# CH32V305RBT6-R1.net
KiCad netlist of a schematic drawn in Altium Designer
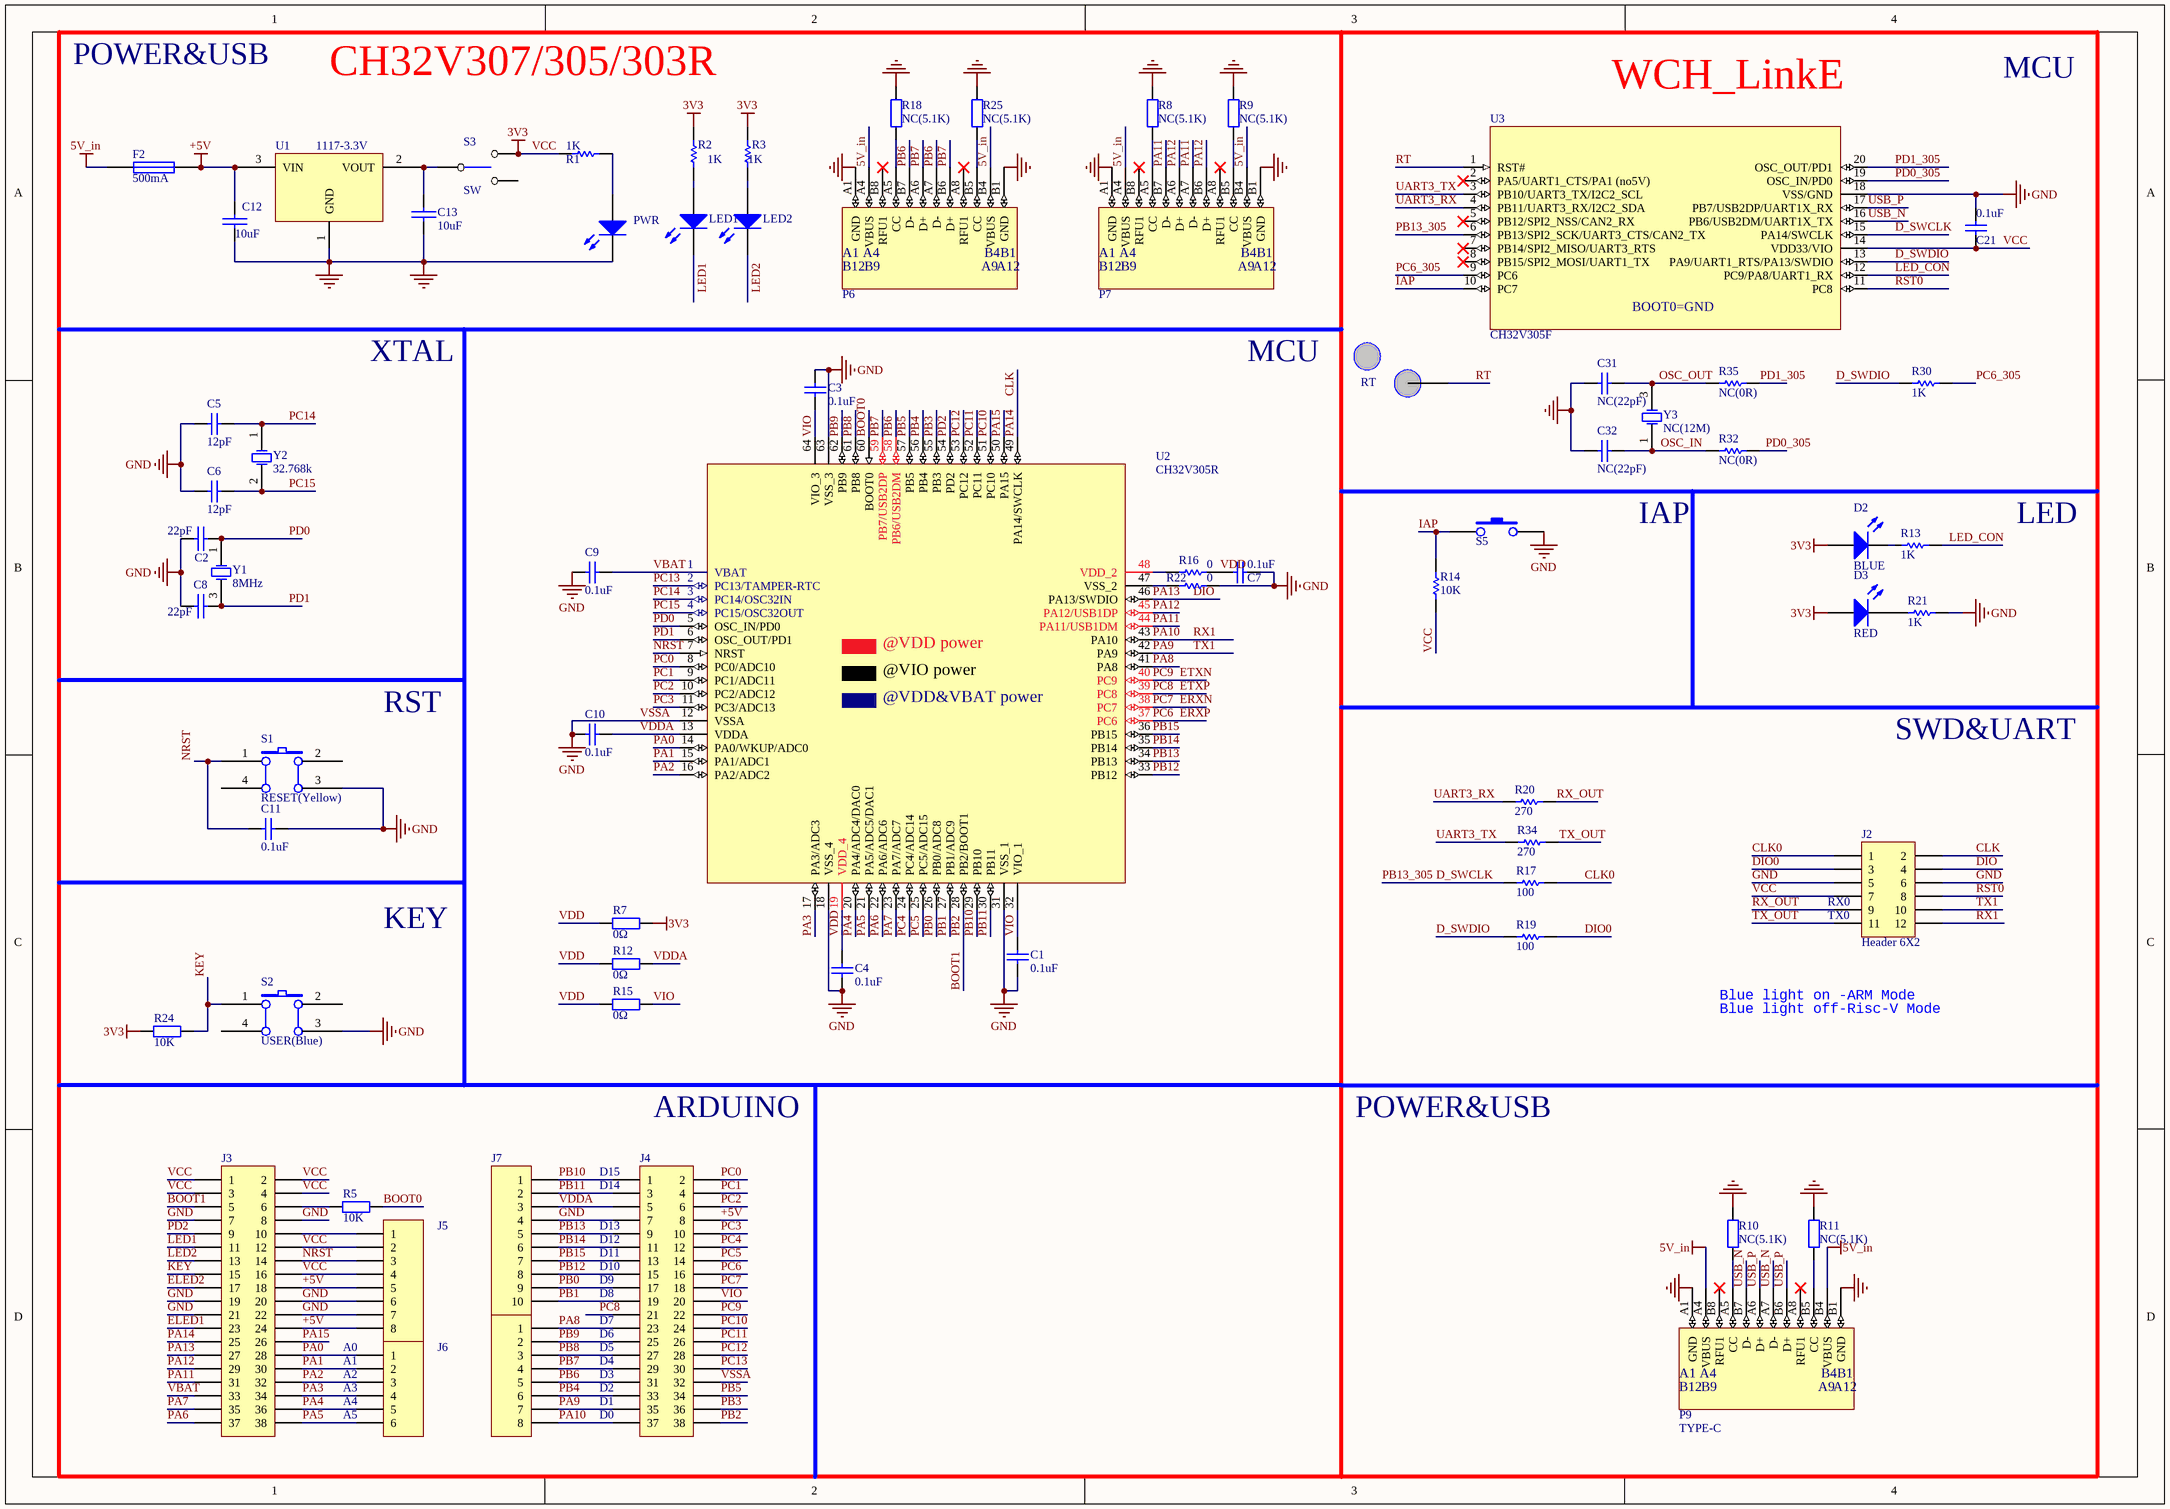
[diagram p0: CH32V305RBT6-R1.SchDoc]

(export (version "E")
  (design (tool "Eeschema 10.0.6"))
  (components
    (comp (ref "C1")
      (value "0.1uF")
      (footprint "0603_C")
      (description "Capacitor")
      (libsource (lib "Miscellaneous Devices") (part "Cap"))
    )
    (comp (ref "C2")
      (value "22pF")
      (footprint "0603_C")
      (description "Capacitor")
      (libsource (lib "*") (part "CAP"))
    )
    (comp (ref "C3")
      (value "0.1uF")
      (footprint "0603_C")
      (description "Capacitor")
      (libsource (lib "Miscellaneous Devices") (part "Cap"))
    )
    (comp (ref "C4")
      (value "0.1uF")
      (footprint "0603_C")
      (description "Capacitor")
      (libsource (lib "Miscellaneous Devices") (part "Cap"))
    )
    (comp (ref "C5")
      (value "12pF")
      (footprint "0603_C")
      (description "Capacitor")
      (libsource (lib "Miscellaneous Devices") (part "Cap"))
    )
    (comp (ref "C6")
      (value "12pF")
      (footprint "0603_C")
      (description "Capacitor")
      (libsource (lib "Miscellaneous Devices") (part "Cap"))
    )
    (comp (ref "C7")
      (value "0.1uF")
      (footprint "0603_C")
      (description "Capacitor")
      (libsource (lib "Miscellaneous Devices") (part "Cap"))
    )
    (comp (ref "C8")
      (value "22pF")
      (footprint "0603_C")
      (description "Capacitor")
      (libsource (lib "*") (part "CAP"))
    )
    (comp (ref "C9")
      (value "0.1uF")
      (footprint "0603_C")
      (description "Capacitor")
      (libsource (lib "Miscellaneous Devices") (part "Cap"))
    )
    (comp (ref "C10")
      (value "0.1uF")
      (footprint "0603_C")
      (description "Capacitor")
      (libsource (lib "Miscellaneous Devices") (part "Cap"))
    )
    (comp (ref "C11")
      (value "0.1uF")
      (footprint "0603_C")
      (description "Capacitor")
      (libsource (lib "Miscellaneous Devices") (part "Cap"))
    )
    (comp (ref "C12")
      (value "10uF")
      (footprint "3216_C")
      (description "Capacitor")
      (libsource (lib "*") (part "CAP"))
    )
    (comp (ref "C13")
      (value "10uF")
      (footprint "3216_C")
      (description "Capacitor")
      (libsource (lib "*") (part "CAP"))
    )
    (comp (ref "C21")
      (value "0.1uF")
      (footprint "0603_C")
      (description "Capacitor")
      (libsource (lib "Miscellaneous Devices") (part "Cap"))
    )
    (comp (ref "C31")
      (value "NC(22pF)")
      (footprint "0603_C")
      (description "Capacitor")
      (fields (field (name "PUBLISHER") "Altium Limited"))
      (libsource (lib "*") (part "Cap"))
    )
    (comp (ref "C32")
      (value "NC(22pF)")
      (footprint "0603_C")
      (description "Capacitor")
      (fields (field (name "PUBLISHER") "Altium Limited"))
      (libsource (lib "*") (part "Cap"))
    )
    (comp (ref "D2")
      (value "BLUE")
      (footprint "0603+")
      (description "Typical RED, GREEN, YELLOW, AMBER GaAs LED")
      (fields (field (name "PUBLISHER") "Altium Limited"))
      (libsource (lib "MYLIB") (part "D0603"))
    )
    (comp (ref "D3")
      (value "RED")
      (footprint "0603+")
      (description "Typical RED, GREEN, YELLOW, AMBER GaAs LED")
      (fields (field (name "PUBLISHER") "Altium Limited"))
      (libsource (lib "MYLIB") (part "D0603"))
    )
    (comp (ref "F2")
      (value "500mA")
      (footprint "0805")
      (description "Fuse")
      (libsource (lib "*") (part "FUSE1"))
    )
    (comp (ref "J2")
      (value "Header 6X2")
      (footprint "IDC12-2.54mm")
      (description "Header, 6-Pin, Dual row")
      (fields (field (name "PUBLISHER") "Altium Limited"))
      (libsource (lib "Miscellaneous Connectors") (part "Header 6X2"))
    )
    (comp (ref "J3")
      (value "Header 19X2")
      (footprint "IDC38-2.54mm")
      (description "Header, 19-Pin, Dual row")
      (fields (field (name "PUBLISHER") "Altium Limited"))
      (libsource (lib "Miscellaneous Connectors") (part "Header 19X2"))
    )
    (comp (ref "J4")
      (value "Header 19X2")
      (footprint "IDC38-2.54mm")
      (description "Header, 19-Pin, Dual row")
      (fields (field (name "PUBLISHER") "Altium Limited"))
      (libsource (lib "Miscellaneous Connectors") (part "Header 19X2"))
    )
    (comp (ref "J5")
      (value "Header 8")
      (footprint "SIP8-2.54mm")
      (description "Header, 8-Pin")
      (fields (field (name "PUBLISHER") "Altium Limited"))
      (libsource (lib "") (part "Header 8_1"))
    )
    (comp (ref "J6")
      (value "Header 6")
      (footprint "SIP6-2.54MM")
      (description "Header, 6-Pin")
      (fields (field (name "PUBLISHER") "Altium Limited"))
      (libsource (lib "Miscellaneous Connectors") (part "Header 6"))
    )
    (comp (ref "J7")
      (value "Header 10")
      (footprint "SIP10-2.54mm")
      (description "Header, 10-Pin")
      (fields (field (name "PUBLISHER") "Altium Limited"))
      (libsource (lib "Miscellaneous Connectors") (part "Header 10"))
    )
    (comp (ref "J8")
      (value "Header 8")
      (footprint "SIP8-2.54mm")
      (description "Header, 8-Pin")
      (fields (field (name "PUBLISHER") "Altium Limited"))
      (libsource (lib "Miscellaneous Connectors") (part "Header 8"))
    )
    (comp (ref "LED1")
      (value "LED1   blue")
      (footprint "0603+")
      (description "Typical INFRARED GaAs LED")
      (fields (field (name "PUBLISHER") "Altium Limited"))
      (libsource (lib "Miscellaneous Devices") (part "LED0"))
    )
    (comp (ref "LED2")
      (value "LED2  blue")
      (footprint "0603+")
      (description "Typical INFRARED GaAs LED")
      (fields (field (name "PUBLISHER") "Altium Limited"))
      (libsource (lib "Miscellaneous Devices") (part "LED0"))
    )
    (comp (ref "P6")
      (value "TYPE-C")
      (footprint "TYPE-C-Receptacle-2.0")
      (libsource (lib "*") (part "TYPE-C1"))
    )
    (comp (ref "P7")
      (value "TYPE-C")
      (footprint "TYPE-C-Receptacle-2.0")
      (libsource (lib "*") (part "TYPE-C1"))
    )
    (comp (ref "P9")
      (value "TYPE-C")
      (footprint "TYPE-C-Receptacle-2.0")
      (libsource (lib "*") (part "TYPE-C1"))
    )
    (comp (ref "PWR")
      (value "POWER  red")
      (footprint "0603+")
      (description "Typical INFRARED GaAs LED")
      (fields (field (name "PUBLISHER") "Altium Limited"))
      (libsource (lib "Miscellaneous Devices") (part "LED0"))
    )
    (comp (ref "R1")
      (value "1K")
      (footprint "0603")
      (description "Semiconductor Resistor")
      (libsource (lib "Miscellaneous Devices") (part "Res Semi"))
    )
    (comp (ref "R2")
      (value "1K")
      (footprint "0603")
      (description "Semiconductor Resistor")
      (libsource (lib "Miscellaneous Devices") (part "Res Semi"))
    )
    (comp (ref "R3")
      (value "1K")
      (footprint "0603")
      (description "Semiconductor Resistor")
      (libsource (lib "Miscellaneous Devices") (part "Res Semi"))
    )
    (comp (ref "R5")
      (value "10K")
      (footprint "0603")
      (description "Resistor")
      (libsource (lib "") (part "Res2_1"))
    )
    (comp (ref "R7")
      (value "0Ω")
      (footprint "0603")
      (description "Resistor")
      (libsource (lib "Miscellaneous Devices") (part "Res2"))
    )
    (comp (ref "R8")
      (value "NC(5.1K)")
      (footprint "0603")
      (description "Resistor")
      (libsource (lib "") (part "Res2_3"))
    )
    (comp (ref "R9")
      (value "NC(5.1K)")
      (footprint "0603")
      (description "Resistor")
      (libsource (lib "") (part "Res2_3"))
    )
    (comp (ref "R10")
      (value "NC(5.1K)")
      (footprint "0603")
      (description "Resistor")
      (libsource (lib "") (part "Res2_2"))
    )
    (comp (ref "R11")
      (value "NC(5.1K)")
      (footprint "0603")
      (description "Resistor")
      (libsource (lib "") (part "Res2_2"))
    )
    (comp (ref "R12")
      (value "0Ω")
      (footprint "0603")
      (description "Resistor")
      (libsource (lib "Miscellaneous Devices") (part "Res2"))
    )
    (comp (ref "R13")
      (value "1K")
      (footprint "0603")
      (description "Resistor")
      (fields (field (name "PUBLISHER") "Altium Limited"))
      (libsource (lib "MYLIB") (part "0603-1"))
    )
    (comp (ref "R14")
      (value "10K")
      (footprint "0603")
      (description "Resistor")
      (fields (field (name "PUBLISHER") "Altium Limited"))
      (libsource (lib "MYLIB") (part "0603-1"))
    )
    (comp (ref "R15")
      (value "0Ω")
      (footprint "0603")
      (description "Resistor")
      (libsource (lib "Miscellaneous Devices") (part "Res2"))
    )
    (comp (ref "R16")
      (value "0")
      (footprint "0603")
      (description "Resistor")
      (fields (field (name "PUBLISHER") "Altium Limited"))
      (libsource (lib "MYLIB") (part "0603-1"))
    )
    (comp (ref "R17")
      (value "100")
      (footprint "0603")
      (description "Resistor")
      (fields (field (name "PUBLISHER") "Altium Limited"))
      (libsource (lib "MYLIB") (part "0603-1"))
    )
    (comp (ref "R18")
      (value "NC(5.1K)")
      (footprint "0603")
      (description "Resistor")
      (libsource (lib "") (part "Res2_3"))
    )
    (comp (ref "R19")
      (value "100")
      (footprint "0603")
      (description "Resistor")
      (fields (field (name "PUBLISHER") "Altium Limited"))
      (libsource (lib "MYLIB") (part "0603-1"))
    )
    (comp (ref "R20")
      (value "270")
      (footprint "0603")
      (description "Resistor")
      (fields (field (name "PUBLISHER") "Altium Limited"))
      (libsource (lib "MYLIB") (part "0603-1"))
    )
    (comp (ref "R21")
      (value "1K")
      (footprint "0603")
      (description "Resistor")
      (fields (field (name "PUBLISHER") "Altium Limited"))
      (libsource (lib "MYLIB") (part "0603-1"))
    )
    (comp (ref "R22")
      (value "0")
      (footprint "0603")
      (description "Resistor")
      (fields (field (name "PUBLISHER") "Altium Limited"))
      (libsource (lib "MYLIB") (part "0603-1"))
    )
    (comp (ref "R24")
      (value "10K")
      (footprint "0603")
      (description "Resistor")
      (libsource (lib "Miscellaneous Devices") (part "Res2"))
    )
    (comp (ref "R25")
      (value "NC(5.1K)")
      (footprint "0603")
      (description "Resistor")
      (libsource (lib "") (part "Res2_3"))
    )
    (comp (ref "R30")
      (value "1K")
      (footprint "0603")
      (description "Resistor")
      (fields (field (name "PUBLISHER") "Altium Limited"))
      (libsource (lib "MYLIB") (part "0603-1"))
    )
    (comp (ref "R32")
      (value "NC(0R)")
      (footprint "0603")
      (description "Resistor")
      (fields (field (name "PUBLISHER") "Altium Limited"))
      (libsource (lib "MYLIB") (part "0603-1"))
    )
    (comp (ref "R34")
      (value "270")
      (footprint "0603")
      (description "Resistor")
      (fields (field (name "PUBLISHER") "Altium Limited"))
      (libsource (lib "MYLIB") (part "0603-1"))
    )
    (comp (ref "R35")
      (value "NC(0R)")
      (footprint "0603")
      (description "Resistor")
      (fields (field (name "PUBLISHER") "Altium Limited"))
      (libsource (lib "MYLIB") (part "0603-1"))
    )
    (comp (ref "RT")
      (value "Testpoint")
      (footprint "TESTPOINT1")
      (description "测试点")
      (libsource (lib "wch_sch_others") (part "Testpoint"))
    )
    (comp (ref "S1")
      (value "RESET(Yellow)")
      (footprint "KEYX")
      (description "SE PUSHBUTTON")
      (libsource (lib "Documents") (part "SW PUSHBUTTON"))
    )
    (comp (ref "S2")
      (value "USER(Blue)")
      (footprint "KEYX")
      (description "SE PUSHBUTTON")
      (libsource (lib "Documents") (part "SW PUSHBUTTON"))
    )
    (comp (ref "S3") (value "SW") (footprint "SW1") (libsource (lib "MYSCH") (part "SW")))
    (comp (ref "S5") (value "KEY") (footprint "贴片按键") (libsource (lib "*") (part "KEY")))
    (comp (ref "U1")
      (value "1117-3.3V")
      (footprint "SOT-223")
      (libsource (lib "wch_sch_others") (part "1117-3.3V"))
    )
    (comp (ref "U2")
      (value "CH32V305R")
      (footprint "LQFP64M_10x10")
      (description "RISC-V FPU HD-MCU, 144MHz, USB_480M, USB OTG, 2*CAN, 4*OPA")
      (libsource (lib "CHXXX") (part "CH32V305R"))
    )
    (comp (ref "U3")
      (value "CH32V305F")
      (footprint "TSSOP20")
      (description "RISC-V FPU HD-MCU, 144MHz, USB_480M, CAN, UART*2, SPI")
      (libsource (lib "CHXXX") (part "CH32V305F"))
    )
    (comp (ref "Y1")
      (value "8MHz")
      (footprint "XT3225")
      (description "Crystal Oscillator")
      (fields (field (name "PUBLISHER") "Altium Limited"))
      (libsource (lib "*") (part "XTAL"))
    )
    (comp (ref "Y2")
      (value "32.768k")
      (footprint "FC-135")
      (description "Crystal Oscillator")
      (fields (field (name "PUBLISHER") "Altium Limited"))
      (libsource (lib "Miscellaneous Devices") (part "XTAL"))
    )
    (comp (ref "Y3")
      (value "NC(12M)")
      (footprint "XT3225")
      (description "Crystal Oscillator")
      (libsource (lib "*") (part "XTAL"))
    )
  )
  (nets
    (net (code "1") (name "+5V") (class "Default")
      (node (ref "C12") (pin "1") (pinfunction "1_1") (pintype "passive"))
      (node (ref "F2") (pin "2") (pinfunction "2_2") (pintype "passive"))
      (node (ref "J3") (pin "18") (pinfunction "18_18") (pintype "passive"))
      (node (ref "J3") (pin "24") (pinfunction "24_24") (pintype "passive"))
      (node (ref "J4") (pin "8") (pinfunction "8_8") (pintype "passive"))
      (node (ref "J5") (pin "5") (pinfunction "5_5") (pintype "passive"))
      (node (ref "J5") (pin "8") (pinfunction "8_8") (pintype "passive"))
      (node (ref "U1") (pin "3") (pinfunction "VIN_3") (pintype "passive"))
    )
    (net (code "2") (name "/BOOT0") (class "Default")
      (node (ref "R5") (pin "2") (pinfunction "2_2") (pintype "passive"))
      (node (ref "U2") (pin "60") (pinfunction "BOOT0_60") (pintype "input"))
    )
    (net (code "3") (name "/BOOT1") (class "Default")
      (node (ref "J3") (pin "5") (pinfunction "5_5") (pintype "passive"))
      (node (ref "J4") (pin "38") (pinfunction "38_38") (pintype "passive"))
      (node (ref "U2") (pin "28") (pinfunction "PB2/BOOT1_28") (pintype "bidirectional"))
    )
    (net (code "4") (name "/CLK") (class "Default")
      (node (ref "J2") (pin "2") (pinfunction "2_2") (pintype "passive"))
      (node (ref "J3") (pin "25") (pinfunction "25_25") (pintype "passive"))
      (node (ref "U2") (pin "49") (pinfunction "PA14/SWCLK_49") (pintype "bidirectional"))
    )
    (net (code "5") (name "/CLK0") (class "Default")
      (node (ref "J2") (pin "1") (pinfunction "1_1") (pintype "passive"))
      (node (ref "R17") (pin "1") (pinfunction "1_1") (pintype "passive"))
    )
    (net (code "6") (name "/DIO") (class "Default")
      (node (ref "J2") (pin "4") (pinfunction "4_4") (pintype "passive"))
      (node (ref "J3") (pin "27") (pinfunction "27_27") (pintype "passive"))
      (node (ref "U2") (pin "46") (pinfunction "PA13/SWDIO_46") (pintype "bidirectional"))
    )
    (net (code "7") (name "/DIO0") (class "Default")
      (node (ref "J2") (pin "3") (pinfunction "3_3") (pintype "passive"))
      (node (ref "R19") (pin "1") (pinfunction "1_1") (pintype "passive"))
    )
    (net (code "8") (name "/D_SWCLK") (class "Default")
      (node (ref "R17") (pin "2") (pinfunction "2_2") (pintype "passive"))
      (node (ref "U3") (pin "15") (pinfunction "PA14/SWCLK_15") (pintype "bidirectional"))
      (node (ref "U3") (pin "6") (pinfunction "PB13/SPI2_SCK/UART3_CTS/CAN2_TX_6") (pintype "bidirectional"))
    )
    (net (code "9") (name "/D_SWDIO") (class "Default")
      (node (ref "R19") (pin "2") (pinfunction "2_2") (pintype "passive"))
      (node (ref "R30") (pin "1") (pinfunction "1_1") (pintype "passive"))
      (node (ref "U3") (pin "13") (pinfunction "PA9/UART1_RTS/PA13/SWDIO_13") (pintype "bidirectional"))
    )
    (net (code "10") (name "/ELED1") (class "Default")
      (node (ref "J3") (pin "23") (pinfunction "23_23") (pintype "passive"))
    )
    (net (code "11") (name "/ELED2") (class "Default")
      (node (ref "J3") (pin "17") (pinfunction "17_17") (pintype "passive"))
    )
    (net (code "12") (name "/ERXN") (class "Default")
      (node (ref "J4") (pin "18") (pinfunction "18_18") (pintype "passive"))
      (node (ref "U2") (pin "38") (pinfunction "PC7_38") (pintype "bidirectional"))
    )
    (net (code "13") (name "/ERXP") (class "Default")
      (node (ref "J4") (pin "16") (pinfunction "16_16") (pintype "passive"))
      (node (ref "U2") (pin "37") (pinfunction "PC6_37") (pintype "bidirectional"))
    )
    (net (code "14") (name "/ETXN") (class "Default")
      (node (ref "J4") (pin "22") (pinfunction "22_22") (pintype "passive"))
      (node (ref "U2") (pin "40") (pinfunction "PC9_40") (pintype "bidirectional"))
    )
    (net (code "15") (name "/ETXP") (class "Default")
      (node (ref "J4") (pin "21") (pinfunction "21_21") (pintype "passive"))
      (node (ref "U2") (pin "39") (pinfunction "PC8_39") (pintype "bidirectional"))
    )
    (net (code "16") (name "/IAP") (class "Default")
      (node (ref "R14") (pin "1") (pinfunction "1_1") (pintype "passive"))
      (node (ref "S5") (pin "1") (pinfunction "1_1") (pintype "passive"))
      (node (ref "U3") (pin "10") (pinfunction "PC7_10") (pintype "bidirectional"))
    )
    (net (code "17") (name "/KEY") (class "Default")
      (node (ref "J3") (pin "15") (pinfunction "15_15") (pintype "passive"))
      (node (ref "R24") (pin "1") (pinfunction "1_1") (pintype "passive"))
      (node (ref "S2") (pin "1") (pinfunction "A0_1") (pintype "passive"))
    )
    (net (code "18") (name "/LED1") (class "Default")
      (node (ref "J3") (pin "11") (pinfunction "11_11") (pintype "passive"))
      (node (ref "LED1") (pin "2") (pinfunction "K_2") (pintype "passive"))
    )
    (net (code "19") (name "/LED2") (class "Default")
      (node (ref "J3") (pin "13") (pinfunction "13_13") (pintype "passive"))
      (node (ref "LED2") (pin "2") (pinfunction "K_2") (pintype "passive"))
    )
    (net (code "20") (name "/LED_CON") (class "Default")
      (node (ref "R13") (pin "1") (pinfunction "1_1") (pintype "passive"))
      (node (ref "U3") (pin "12") (pinfunction "PC9/PA8/UART1_RX_12") (pintype "bidirectional"))
    )
    (net (code "21") (name "/NRST") (class "Default")
      (node (ref "C11") (pin "2") (pinfunction "2_2") (pintype "passive"))
      (node (ref "J3") (pin "14") (pinfunction "14_14") (pintype "passive"))
      (node (ref "J5") (pin "3") (pinfunction "3_3") (pintype "passive"))
      (node (ref "S1") (pin "1") (pinfunction "A0_1") (pintype "passive"))
      (node (ref "U2") (pin "7") (pinfunction "NRST_7") (pintype "input"))
    )
    (net (code "22") (name "/OSC_IN") (class "Default")
      (node (ref "C32") (pin "2") (pinfunction "2_2") (pintype "passive"))
      (node (ref "R32") (pin "2") (pinfunction "2_2") (pintype "passive"))
      (node (ref "Y3") (pin "1") (pinfunction "OSC1_1") (pintype "passive"))
    )
    (net (code "23") (name "/OSC_OUT") (class "Default")
      (node (ref "C31") (pin "2") (pinfunction "2_2") (pintype "passive"))
      (node (ref "R35") (pin "2") (pinfunction "2_2") (pintype "passive"))
      (node (ref "Y3") (pin "3") (pinfunction "OSC2_3") (pintype "passive"))
    )
    (net (code "24") (name "/PA0") (class "Default")
      (node (ref "J3") (pin "28") (pinfunction "28_28") (pintype "passive"))
      (node (ref "J6") (pin "1") (pinfunction "1_1") (pintype "passive"))
      (node (ref "U2") (pin "14") (pinfunction "PA0/WKUP/ADC0_14") (pintype "bidirectional"))
    )
    (net (code "25") (name "/PA1") (class "Default")
      (node (ref "J3") (pin "30") (pinfunction "30_30") (pintype "passive"))
      (node (ref "J6") (pin "2") (pinfunction "2_2") (pintype "passive"))
      (node (ref "U2") (pin "15") (pinfunction "PA1/ADC1_15") (pintype "bidirectional"))
    )
    (net (code "26") (name "/PA2") (class "Default")
      (node (ref "J3") (pin "32") (pinfunction "32_32") (pintype "passive"))
      (node (ref "J6") (pin "3") (pinfunction "3_3") (pintype "passive"))
      (node (ref "U2") (pin "16") (pinfunction "PA2/ADC2_16") (pintype "bidirectional"))
    )
    (net (code "27") (name "/PA3") (class "Default")
      (node (ref "J3") (pin "34") (pinfunction "34_34") (pintype "passive"))
      (node (ref "J6") (pin "4") (pinfunction "4_4") (pintype "passive"))
      (node (ref "U2") (pin "17") (pinfunction "PA3/ADC3_17") (pintype "bidirectional"))
    )
    (net (code "28") (name "/PA4") (class "Default")
      (node (ref "J3") (pin "36") (pinfunction "36_36") (pintype "passive"))
      (node (ref "J6") (pin "5") (pinfunction "5_5") (pintype "passive"))
      (node (ref "U2") (pin "20") (pinfunction "PA4/ADC4/DAC0_20") (pintype "bidirectional"))
    )
    (net (code "29") (name "/PA5") (class "Default")
      (node (ref "J3") (pin "38") (pinfunction "38_38") (pintype "passive"))
      (node (ref "J6") (pin "6") (pinfunction "6_6") (pintype "passive"))
      (node (ref "U2") (pin "21") (pinfunction "PA5/ADC5/DAC1_21") (pintype "bidirectional"))
    )
    (net (code "30") (name "/PA6") (class "Default")
      (node (ref "J3") (pin "37") (pinfunction "37_37") (pintype "passive"))
      (node (ref "U2") (pin "22") (pinfunction "PA6/ADC6_22") (pintype "bidirectional"))
    )
    (net (code "31") (name "/PA7") (class "Default")
      (node (ref "J3") (pin "35") (pinfunction "35_35") (pintype "passive"))
      (node (ref "U2") (pin "23") (pinfunction "PA7/ADC7_23") (pintype "bidirectional"))
    )
    (net (code "32") (name "/PA8") (class "Default")
      (node (ref "J4") (pin "23") (pinfunction "23_23") (pintype "passive"))
      (node (ref "J8") (pin "1") (pinfunction "1_1") (pintype "passive"))
      (node (ref "U2") (pin "41") (pinfunction "PA8_41") (pintype "bidirectional"))
    )
    (net (code "33") (name "/PA9") (class "Default")
      (node (ref "J2") (pin "10") (pinfunction "10_10") (pintype "passive"))
      (node (ref "J4") (pin "35") (pinfunction "35_35") (pintype "passive"))
      (node (ref "J8") (pin "7") (pinfunction "7_7") (pintype "passive"))
      (node (ref "U2") (pin "42") (pinfunction "PA9_42") (pintype "bidirectional"))
    )
    (net (code "34") (name "/PA10") (class "Default")
      (node (ref "J2") (pin "12") (pinfunction "12_12") (pintype "passive"))
      (node (ref "J4") (pin "37") (pinfunction "37_37") (pintype "passive"))
      (node (ref "J8") (pin "8") (pinfunction "8_8") (pintype "passive"))
      (node (ref "U2") (pin "43") (pinfunction "PA10_43") (pintype "bidirectional"))
    )
    (net (code "35") (name "/PA11") (class "Default")
      (node (ref "J3") (pin "31") (pinfunction "31_31") (pintype "passive"))
      (node (ref "P7") (pin "A7") (pinfunction "D-_A7") (pintype "bidirectional"))
      (node (ref "P7") (pin "B7") (pinfunction "D-_B7") (pintype "bidirectional"))
      (node (ref "U2") (pin "44") (pinfunction "PA11/USB1DM_44") (pintype "bidirectional"))
    )
    (net (code "36") (name "/PA12") (class "Default")
      (node (ref "J3") (pin "29") (pinfunction "29_29") (pintype "passive"))
      (node (ref "P7") (pin "A6") (pinfunction "D+_A6") (pintype "bidirectional"))
      (node (ref "P7") (pin "B6") (pinfunction "D+_B6") (pintype "bidirectional"))
      (node (ref "U2") (pin "45") (pinfunction "PA12/USB1DP_45") (pintype "bidirectional"))
    )
    (net (code "37") (name "/PA15") (class "Default")
      (node (ref "J3") (pin "26") (pinfunction "26_26") (pintype "passive"))
      (node (ref "U2") (pin "50") (pinfunction "PA15_50") (pintype "bidirectional"))
    )
    (net (code "38") (name "/PB0") (class "Default")
      (node (ref "J4") (pin "17") (pinfunction "17_17") (pintype "passive"))
      (node (ref "J7") (pin "9") (pinfunction "9_9") (pintype "passive"))
      (node (ref "U2") (pin "26") (pinfunction "PB0/ADC8_26") (pintype "bidirectional"))
    )
    (net (code "39") (name "/PB1") (class "Default")
      (node (ref "J4") (pin "19") (pinfunction "19_19") (pintype "passive"))
      (node (ref "J7") (pin "10") (pinfunction "10_10") (pintype "passive"))
      (node (ref "U2") (pin "27") (pinfunction "PB1/ADC9_27") (pintype "bidirectional"))
    )
    (net (code "40") (name "/PB3") (class "Default")
      (node (ref "J4") (pin "36") (pinfunction "36_36") (pintype "passive"))
      (node (ref "U2") (pin "55") (pinfunction "PB3_55") (pintype "bidirectional"))
    )
    (net (code "41") (name "/PB4") (class "Default")
      (node (ref "J4") (pin "33") (pinfunction "33_33") (pintype "passive"))
      (node (ref "J8") (pin "6") (pinfunction "6_6") (pintype "passive"))
      (node (ref "U2") (pin "56") (pinfunction "PB4_56") (pintype "bidirectional"))
    )
    (net (code "42") (name "/PB5") (class "Default")
      (node (ref "J4") (pin "34") (pinfunction "34_34") (pintype "passive"))
      (node (ref "U2") (pin "57") (pinfunction "PB5_57") (pintype "bidirectional"))
    )
    (net (code "43") (name "/PB6") (class "Default")
      (node (ref "J4") (pin "31") (pinfunction "31_31") (pintype "passive"))
      (node (ref "J8") (pin "5") (pinfunction "5_5") (pintype "passive"))
      (node (ref "P6") (pin "A7") (pinfunction "D-_A7") (pintype "bidirectional"))
      (node (ref "P6") (pin "B7") (pinfunction "D-_B7") (pintype "bidirectional"))
      (node (ref "U2") (pin "58") (pinfunction "PB6/USB2DM_58") (pintype "bidirectional"))
    )
    (net (code "44") (name "/PB7") (class "Default")
      (node (ref "J4") (pin "29") (pinfunction "29_29") (pintype "passive"))
      (node (ref "J8") (pin "4") (pinfunction "4_4") (pintype "passive"))
      (node (ref "P6") (pin "A6") (pinfunction "D+_A6") (pintype "bidirectional"))
      (node (ref "P6") (pin "B6") (pinfunction "D+_B6") (pintype "bidirectional"))
      (node (ref "U2") (pin "59") (pinfunction "PB7/USB2DP_59") (pintype "bidirectional"))
    )
    (net (code "45") (name "/PB8") (class "Default")
      (node (ref "J4") (pin "27") (pinfunction "27_27") (pintype "passive"))
      (node (ref "J8") (pin "3") (pinfunction "3_3") (pintype "passive"))
      (node (ref "U2") (pin "61") (pinfunction "PB8_61") (pintype "bidirectional"))
    )
    (net (code "46") (name "/PB9") (class "Default")
      (node (ref "J4") (pin "25") (pinfunction "25_25") (pintype "passive"))
      (node (ref "J8") (pin "2") (pinfunction "2_2") (pintype "passive"))
      (node (ref "U2") (pin "62") (pinfunction "PB9_62") (pintype "bidirectional"))
    )
    (net (code "47") (name "/PB10") (class "Default")
      (node (ref "J4") (pin "1") (pinfunction "1_1") (pintype "passive"))
      (node (ref "J7") (pin "1") (pinfunction "1_1") (pintype "passive"))
      (node (ref "U2") (pin "29") (pinfunction "PB10_29") (pintype "bidirectional"))
    )
    (net (code "48") (name "/PB11") (class "Default")
      (node (ref "J4") (pin "3") (pinfunction "3_3") (pintype "passive"))
      (node (ref "J7") (pin "2") (pinfunction "2_2") (pintype "passive"))
      (node (ref "U2") (pin "30") (pinfunction "PB11_30") (pintype "bidirectional"))
    )
    (net (code "49") (name "/PB12") (class "Default")
      (node (ref "J4") (pin "15") (pinfunction "15_15") (pintype "passive"))
      (node (ref "J7") (pin "8") (pinfunction "8_8") (pintype "passive"))
      (node (ref "U2") (pin "33") (pinfunction "PB12_33") (pintype "bidirectional"))
    )
    (net (code "50") (name "/PB13") (class "Default")
      (node (ref "J4") (pin "9") (pinfunction "9_9") (pintype "passive"))
      (node (ref "J7") (pin "5") (pinfunction "5_5") (pintype "passive"))
      (node (ref "U2") (pin "34") (pinfunction "PB13_34") (pintype "bidirectional"))
    )
    (net (code "51") (name "/PB14") (class "Default")
      (node (ref "J4") (pin "11") (pinfunction "11_11") (pintype "passive"))
      (node (ref "J7") (pin "6") (pinfunction "6_6") (pintype "passive"))
      (node (ref "U2") (pin "35") (pinfunction "PB14_35") (pintype "bidirectional"))
    )
    (net (code "52") (name "/PB15") (class "Default")
      (node (ref "J4") (pin "13") (pinfunction "13_13") (pintype "passive"))
      (node (ref "J7") (pin "7") (pinfunction "7_7") (pintype "passive"))
      (node (ref "U2") (pin "36") (pinfunction "PB15_36") (pintype "bidirectional"))
    )
    (net (code "53") (name "/PC0") (class "Default")
      (node (ref "J4") (pin "2") (pinfunction "2_2") (pintype "passive"))
      (node (ref "U2") (pin "8") (pinfunction "PC0/ADC10_8") (pintype "bidirectional"))
    )
    (net (code "54") (name "/PC1") (class "Default")
      (node (ref "J4") (pin "4") (pinfunction "4_4") (pintype "passive"))
      (node (ref "U2") (pin "9") (pinfunction "PC1/ADC11_9") (pintype "bidirectional"))
    )
    (net (code "55") (name "/PC2") (class "Default")
      (node (ref "J4") (pin "6") (pinfunction "6_6") (pintype "passive"))
      (node (ref "U2") (pin "10") (pinfunction "PC2/ADC12_10") (pintype "bidirectional"))
    )
    (net (code "56") (name "/PC3") (class "Default")
      (node (ref "J4") (pin "10") (pinfunction "10_10") (pintype "passive"))
      (node (ref "U2") (pin "11") (pinfunction "PC3/ADC13_11") (pintype "bidirectional"))
    )
    (net (code "57") (name "/PC4") (class "Default")
      (node (ref "J4") (pin "12") (pinfunction "12_12") (pintype "passive"))
      (node (ref "U2") (pin "24") (pinfunction "PC4/ADC14_24") (pintype "bidirectional"))
    )
    (net (code "58") (name "/PC5") (class "Default")
      (node (ref "J4") (pin "14") (pinfunction "14_14") (pintype "passive"))
      (node (ref "U2") (pin "25") (pinfunction "PC5/ADC15_25") (pintype "bidirectional"))
    )
    (net (code "59") (name "/PC6_305") (class "Default")
      (node (ref "R30") (pin "2") (pinfunction "2_2") (pintype "passive"))
      (node (ref "U3") (pin "9") (pinfunction "PC6_9") (pintype "bidirectional"))
    )
    (net (code "60") (name "/PC10") (class "Default")
      (node (ref "J4") (pin "24") (pinfunction "24_24") (pintype "passive"))
      (node (ref "U2") (pin "51") (pinfunction "PC10_51") (pintype "bidirectional"))
    )
    (net (code "61") (name "/PC11") (class "Default")
      (node (ref "J4") (pin "26") (pinfunction "26_26") (pintype "passive"))
      (node (ref "U2") (pin "52") (pinfunction "PC11_52") (pintype "bidirectional"))
    )
    (net (code "62") (name "/PC12") (class "Default")
      (node (ref "J4") (pin "28") (pinfunction "28_28") (pintype "passive"))
      (node (ref "U2") (pin "53") (pinfunction "PC12_53") (pintype "bidirectional"))
    )
    (net (code "63") (name "/PC13") (class "Default")
      (node (ref "J4") (pin "30") (pinfunction "30_30") (pintype "passive"))
      (node (ref "U2") (pin "2") (pinfunction "PC13/TAMPER-RTC_2") (pintype "bidirectional"))
    )
    (net (code "64") (name "/PC14") (class "Default")
      (node (ref "C5") (pin "1") (pinfunction "1_1") (pintype "passive"))
      (node (ref "U2") (pin "3") (pinfunction "PC14/OSC32IN_3") (pintype "bidirectional"))
      (node (ref "Y2") (pin "1") (pinfunction "OSC1_1") (pintype "passive"))
    )
    (net (code "65") (name "/PC15") (class "Default")
      (node (ref "C6") (pin "1") (pinfunction "1_1") (pintype "passive"))
      (node (ref "U2") (pin "4") (pinfunction "PC15/OSC32OUT_4") (pintype "bidirectional"))
      (node (ref "Y2") (pin "2") (pinfunction "OSC2_2") (pintype "passive"))
    )
    (net (code "66") (name "/PD0") (class "Default")
      (node (ref "C2") (pin "2") (pinfunction "2_2") (pintype "passive"))
      (node (ref "U2") (pin "5") (pinfunction "OSC_IN/PD0_5") (pintype "bidirectional"))
      (node (ref "Y1") (pin "1") (pinfunction "OSC1_1") (pintype "passive"))
    )
    (net (code "67") (name "/PD0_305") (class "Default")
      (node (ref "R32") (pin "1") (pinfunction "1_1") (pintype "passive"))
      (node (ref "U3") (pin "19") (pinfunction "OSC_IN/PD0_19") (pintype "bidirectional"))
    )
    (net (code "68") (name "/PD1") (class "Default")
      (node (ref "C8") (pin "2") (pinfunction "2_2") (pintype "passive"))
      (node (ref "U2") (pin "6") (pinfunction "OSC_OUT/PD1_6") (pintype "bidirectional"))
      (node (ref "Y1") (pin "3") (pinfunction "OSC2_3") (pintype "passive"))
    )
    (net (code "69") (name "/PD1_305") (class "Default")
      (node (ref "R35") (pin "1") (pinfunction "1_1") (pintype "passive"))
      (node (ref "U3") (pin "20") (pinfunction "OSC_OUT/PD1_20") (pintype "bidirectional"))
    )
    (net (code "70") (name "/PD2") (class "Default")
      (node (ref "J3") (pin "9") (pinfunction "9_9") (pintype "passive"))
      (node (ref "U2") (pin "54") (pinfunction "PD2_54") (pintype "bidirectional"))
    )
    (net (code "71") (name "/RST0") (class "Default")
      (node (ref "J2") (pin "8") (pinfunction "8_8") (pintype "passive"))
      (node (ref "U3") (pin "11") (pinfunction "PC8_11") (pintype "bidirectional"))
    )
    (net (code "72") (name "/RT") (class "Default")
      (node (ref "RT") (pin "1") (pinfunction "point_1") (pintype "passive"))
      (node (ref "U3") (pin "1") (pinfunction "RST#_1") (pintype "input"))
    )
    (net (code "73") (name "/RX_OUT") (class "Default")
      (node (ref "J2") (pin "9") (pinfunction "9_9") (pintype "passive"))
      (node (ref "R20") (pin "1") (pinfunction "1_1") (pintype "passive"))
    )
    (net (code "74") (name "/TX_OUT") (class "Default")
      (node (ref "J2") (pin "11") (pinfunction "11_11") (pintype "passive"))
      (node (ref "R34") (pin "1") (pinfunction "1_1") (pintype "passive"))
    )
    (net (code "75") (name "/UART3_RX") (class "Default")
      (node (ref "R20") (pin "2") (pinfunction "2_2") (pintype "passive"))
      (node (ref "U3") (pin "4") (pinfunction "PB11/UART3_RX/I2C2_SDA_4") (pintype "bidirectional"))
    )
    (net (code "76") (name "/UART3_TX") (class "Default")
      (node (ref "R34") (pin "2") (pinfunction "2_2") (pintype "passive"))
      (node (ref "U3") (pin "3") (pinfunction "PB10/UART3_TX/I2C2_SCL_3") (pintype "bidirectional"))
    )
    (net (code "77") (name "/USB_N") (class "Default")
      (node (ref "P9") (pin "A7") (pinfunction "D-_A7") (pintype "bidirectional"))
      (node (ref "P9") (pin "B7") (pinfunction "D-_B7") (pintype "bidirectional"))
      (node (ref "U3") (pin "16") (pinfunction "PB6/USB2DM/UART1X_TX_16") (pintype "bidirectional"))
    )
    (net (code "78") (name "/USB_P") (class "Default")
      (node (ref "P9") (pin "A6") (pinfunction "D+_A6") (pintype "bidirectional"))
      (node (ref "P9") (pin "B6") (pinfunction "D+_B6") (pintype "bidirectional"))
      (node (ref "U3") (pin "17") (pinfunction "PB7/USB2DP/UART1X_RX_17") (pintype "bidirectional"))
    )
    (net (code "79") (name "/VBAT") (class "Default")
      (node (ref "C9") (pin "1") (pinfunction "1_1") (pintype "passive"))
      (node (ref "J3") (pin "33") (pinfunction "33_33") (pintype "passive"))
      (node (ref "U2") (pin "1") (pinfunction "VBAT_1") (pintype "power_in"))
    )
    (net (code "80") (name "/VDD") (class "Default")
      (node (ref "C4") (pin "2") (pinfunction "2_2") (pintype "passive"))
      (node (ref "C7") (pin "2") (pinfunction "2_2") (pintype "passive"))
      (node (ref "R12") (pin "2") (pinfunction "2_2") (pintype "passive"))
      (node (ref "R15") (pin "2") (pinfunction "2_2") (pintype "passive"))
      (node (ref "R16") (pin "1") (pinfunction "1_1") (pintype "passive"))
      (node (ref "R7") (pin "2") (pinfunction "2_2") (pintype "passive"))
      (node (ref "U2") (pin "19") (pinfunction "VDD_4_19") (pintype "power_in"))
    )
    (net (code "81") (name "/VDDA") (class "Default")
      (node (ref "C10") (pin "1") (pinfunction "1_1") (pintype "passive"))
      (node (ref "J4") (pin "5") (pinfunction "5_5") (pintype "passive"))
      (node (ref "J7") (pin "3") (pinfunction "3_3") (pintype "passive"))
      (node (ref "R12") (pin "1") (pinfunction "1_1") (pintype "passive"))
      (node (ref "U2") (pin "13") (pinfunction "VDDA_13") (pintype "power_in"))
    )
    (net (code "82") (name "/VIO") (class "Default")
      (node (ref "C1") (pin "2") (pinfunction "2_2") (pintype "passive"))
      (node (ref "C3") (pin "2") (pinfunction "2_2") (pintype "passive"))
      (node (ref "J4") (pin "20") (pinfunction "20_20") (pintype "passive"))
      (node (ref "R15") (pin "1") (pinfunction "1_1") (pintype "passive"))
      (node (ref "U2") (pin "32") (pinfunction "VIO_1_32") (pintype "power_in"))
      (node (ref "U2") (pin "64") (pinfunction "VIO_3_64") (pintype "power_in"))
    )
    (net (code "83") (name "3V3") (class "Default")
      (node (ref "C21") (pin "1") (pinfunction "1_1") (pintype "passive"))
      (node (ref "D2") (pin "1") (pinfunction "A_1") (pintype "passive"))
      (node (ref "D3") (pin "1") (pinfunction "A_1") (pintype "passive"))
      (node (ref "J2") (pin "7") (pinfunction "7_7") (pintype "passive"))
      (node (ref "J3") (pin "1") (pinfunction "1_1") (pintype "passive"))
      (node (ref "J3") (pin "12") (pinfunction "12_12") (pintype "passive"))
      (node (ref "J3") (pin "16") (pinfunction "16_16") (pintype "passive"))
      (node (ref "J3") (pin "2") (pinfunction "2_2") (pintype "passive"))
      (node (ref "J3") (pin "3") (pinfunction "3_3") (pintype "passive"))
      (node (ref "J3") (pin "4") (pinfunction "4_4") (pintype "passive"))
      (node (ref "J5") (pin "2") (pinfunction "2_2") (pintype "passive"))
      (node (ref "J5") (pin "4") (pinfunction "4_4") (pintype "passive"))
      (node (ref "R1") (pin "2") (pinfunction "2_2") (pintype "passive"))
      (node (ref "R14") (pin "2") (pinfunction "2_2") (pintype "passive"))
      (node (ref "R2") (pin "1") (pinfunction "1_1") (pintype "passive"))
      (node (ref "R24") (pin "2") (pinfunction "2_2") (pintype "passive"))
      (node (ref "R3") (pin "1") (pinfunction "1_1") (pintype "passive"))
      (node (ref "R7") (pin "1") (pinfunction "1_1") (pintype "passive"))
      (node (ref "S3") (pin "3") (pinfunction "3_3") (pintype "passive"))
      (node (ref "U3") (pin "14") (pinfunction "VDD33/VIO_14") (pintype "power_in"))
    )
    (net (code "84") (name "5V_in") (class "Default")
      (node (ref "F2") (pin "1") (pinfunction "1_1") (pintype "passive"))
      (node (ref "P6") (pin "A4") (pinfunction "VBUS_A4") (pintype "bidirectional"))
      (node (ref "P6") (pin "B4") (pinfunction "VBUS_B4") (pintype "bidirectional"))
      (node (ref "P7") (pin "A4") (pinfunction "VBUS_A4") (pintype "bidirectional"))
      (node (ref "P7") (pin "B4") (pinfunction "VBUS_B4") (pintype "bidirectional"))
      (node (ref "P9") (pin "A4") (pinfunction "VBUS_A4") (pintype "bidirectional"))
      (node (ref "P9") (pin "B4") (pinfunction "VBUS_B4") (pintype "bidirectional"))
    )
    (net (code "85") (name "GND") (class "Default")
      (node (ref "C1") (pin "1") (pinfunction "1_1") (pintype "passive"))
      (node (ref "C10") (pin "2") (pinfunction "2_2") (pintype "passive"))
      (node (ref "C11") (pin "1") (pinfunction "1_1") (pintype "passive"))
      (node (ref "C12") (pin "2") (pinfunction "2_2") (pintype "passive"))
      (node (ref "C13") (pin "2") (pinfunction "2_2") (pintype "passive"))
      (node (ref "C2") (pin "1") (pinfunction "1_1") (pintype "passive"))
      (node (ref "C21") (pin "2") (pinfunction "2_2") (pintype "passive"))
      (node (ref "C3") (pin "1") (pinfunction "1_1") (pintype "passive"))
      (node (ref "C31") (pin "1") (pinfunction "1_1") (pintype "passive"))
      (node (ref "C32") (pin "1") (pinfunction "1_1") (pintype "passive"))
      (node (ref "C4") (pin "1") (pinfunction "1_1") (pintype "passive"))
      (node (ref "C5") (pin "2") (pinfunction "2_2") (pintype "passive"))
      (node (ref "C6") (pin "2") (pinfunction "2_2") (pintype "passive"))
      (node (ref "C7") (pin "1") (pinfunction "1_1") (pintype "passive"))
      (node (ref "C8") (pin "1") (pinfunction "1_1") (pintype "passive"))
      (node (ref "C9") (pin "2") (pinfunction "2_2") (pintype "passive"))
      (node (ref "J2") (pin "5") (pinfunction "5_5") (pintype "passive"))
      (node (ref "J2") (pin "6") (pinfunction "6_6") (pintype "passive"))
      (node (ref "J3") (pin "19") (pinfunction "19_19") (pintype "passive"))
      (node (ref "J3") (pin "20") (pinfunction "20_20") (pintype "passive"))
      (node (ref "J3") (pin "21") (pinfunction "21_21") (pintype "passive"))
      (node (ref "J3") (pin "22") (pinfunction "22_22") (pintype "passive"))
      (node (ref "J3") (pin "7") (pinfunction "7_7") (pintype "passive"))
      (node (ref "J3") (pin "8") (pinfunction "8_8") (pintype "passive"))
      (node (ref "J4") (pin "32") (pinfunction "32_32") (pintype "passive"))
      (node (ref "J4") (pin "7") (pinfunction "7_7") (pintype "passive"))
      (node (ref "J5") (pin "6") (pinfunction "6_6") (pintype "passive"))
      (node (ref "J5") (pin "7") (pinfunction "7_7") (pintype "passive"))
      (node (ref "J7") (pin "4") (pinfunction "4_4") (pintype "passive"))
      (node (ref "P6") (pin "A1") (pinfunction "GND_A1") (pintype "bidirectional"))
      (node (ref "P6") (pin "B1") (pinfunction "GND_B1") (pintype "bidirectional"))
      (node (ref "P7") (pin "A1") (pinfunction "GND_A1") (pintype "bidirectional"))
      (node (ref "P7") (pin "B1") (pinfunction "GND_B1") (pintype "bidirectional"))
      (node (ref "P9") (pin "A1") (pinfunction "GND_A1") (pintype "bidirectional"))
      (node (ref "P9") (pin "B1") (pinfunction "GND_B1") (pintype "bidirectional"))
      (node (ref "PWR") (pin "2") (pinfunction "K_2") (pintype "passive"))
      (node (ref "R10") (pin "2") (pinfunction "2_2") (pintype "passive"))
      (node (ref "R11") (pin "2") (pinfunction "2_2") (pintype "passive"))
      (node (ref "R18") (pin "1") (pinfunction "1_1") (pintype "passive"))
      (node (ref "R21") (pin "1") (pinfunction "1_1") (pintype "passive"))
      (node (ref "R22") (pin "1") (pinfunction "1_1") (pintype "passive"))
      (node (ref "R25") (pin "1") (pinfunction "1_1") (pintype "passive"))
      (node (ref "R8") (pin "1") (pinfunction "1_1") (pintype "passive"))
      (node (ref "R9") (pin "1") (pinfunction "1_1") (pintype "passive"))
      (node (ref "S1") (pin "3") (pinfunction "B1_3") (pintype "passive"))
      (node (ref "S2") (pin "3") (pinfunction "B1_3") (pintype "passive"))
      (node (ref "S5") (pin "2") (pinfunction "2_2") (pintype "passive"))
      (node (ref "U1") (pin "1") (pinfunction "GND_1") (pintype "passive"))
      (node (ref "U2") (pin "12") (pinfunction "VSSA_12") (pintype "power_in"))
      (node (ref "U2") (pin "18") (pinfunction "VSS_4_18") (pintype "power_in"))
      (node (ref "U2") (pin "31") (pinfunction "VSS_1_31") (pintype "power_in"))
      (node (ref "U2") (pin "63") (pinfunction "VSS_3_63") (pintype "power_in"))
      (node (ref "U3") (pin "18") (pinfunction "VSS/GND_18") (pintype "power_in"))
    )
    (net (code "86") (name "Net-(D2-K)") (class "Default")
      (node (ref "D2") (pin "2") (pinfunction "K_2") (pintype "passive"))
      (node (ref "R13") (pin "2") (pinfunction "2_2") (pintype "passive"))
    )
    (net (code "87") (name "Net-(D3-K)") (class "Default")
      (node (ref "D3") (pin "2") (pinfunction "K_2") (pintype "passive"))
      (node (ref "R21") (pin "2") (pinfunction "2_2") (pintype "passive"))
    )
    (net (code "88") (name "Net-(J3-Pad6)") (class "Default")
      (node (ref "J3") (pin "6") (pinfunction "6_6") (pintype "passive"))
      (node (ref "R5") (pin "1") (pinfunction "1_1") (pintype "passive"))
    )
    (net (code "89") (name "Net-(J3-Pad10)") (class "Default")
      (node (ref "J3") (pin "10") (pinfunction "10_10") (pintype "passive"))
      (node (ref "J5") (pin "1") (pinfunction "1_1") (pintype "passive"))
    )
    (net (code "90") (name "Net-(LED1-A)") (class "Default")
      (node (ref "LED1") (pin "1") (pinfunction "A_1") (pintype "passive"))
      (node (ref "R2") (pin "2") (pinfunction "2_2") (pintype "passive"))
    )
    (net (code "91") (name "Net-(LED2-A)") (class "Default")
      (node (ref "LED2") (pin "1") (pinfunction "A_1") (pintype "passive"))
      (node (ref "R3") (pin "2") (pinfunction "2_2") (pintype "passive"))
    )
    (net (code "92") (name "Net-(P6-CC-PadA5)") (class "Default")
      (node (ref "P6") (pin "A5") (pinfunction "CC_A5") (pintype "bidirectional"))
      (node (ref "R18") (pin "2") (pinfunction "2_2") (pintype "passive"))
    )
    (net (code "93") (name "Net-(P6-CC-PadB5)") (class "Default")
      (node (ref "P6") (pin "B5") (pinfunction "CC_B5") (pintype "bidirectional"))
      (node (ref "R25") (pin "2") (pinfunction "2_2") (pintype "passive"))
    )
    (net (code "94") (name "Net-(P7-CC-PadA5)") (class "Default")
      (node (ref "P7") (pin "A5") (pinfunction "CC_A5") (pintype "bidirectional"))
      (node (ref "R8") (pin "2") (pinfunction "2_2") (pintype "passive"))
    )
    (net (code "95") (name "Net-(P7-CC-PadB5)") (class "Default")
      (node (ref "P7") (pin "B5") (pinfunction "CC_B5") (pintype "bidirectional"))
      (node (ref "R9") (pin "2") (pinfunction "2_2") (pintype "passive"))
    )
    (net (code "96") (name "Net-(P9-CC-PadA5)") (class "Default")
      (node (ref "P9") (pin "A5") (pinfunction "CC_A5") (pintype "bidirectional"))
      (node (ref "R10") (pin "1") (pinfunction "1_1") (pintype "passive"))
    )
    (net (code "97") (name "Net-(P9-CC-PadB5)") (class "Default")
      (node (ref "P9") (pin "B5") (pinfunction "CC_B5") (pintype "bidirectional"))
      (node (ref "R11") (pin "1") (pinfunction "1_1") (pintype "passive"))
    )
    (net (code "98") (name "Net-(PWR-A)") (class "Default")
      (node (ref "PWR") (pin "1") (pinfunction "A_1") (pintype "passive"))
      (node (ref "R1") (pin "1") (pinfunction "1_1") (pintype "passive"))
    )
    (net (code "99") (name "Net-(U1-VOUT)") (class "Default")
      (node (ref "C13") (pin "1") (pinfunction "1_1") (pintype "passive"))
      (node (ref "S3") (pin "1") (pinfunction "1_1") (pintype "passive"))
      (node (ref "U1") (pin "2") (pinfunction "VOUT_2") (pintype "passive"))
    )
    (net (code "100") (name "Net-(U2-VDD_2)") (class "Default")
      (node (ref "R16") (pin "2") (pinfunction "2_2") (pintype "passive"))
      (node (ref "U2") (pin "48") (pinfunction "VDD_2_48") (pintype "power_in"))
    )
    (net (code "101") (name "Net-(U2-VSS_2)") (class "Default")
      (node (ref "R22") (pin "2") (pinfunction "2_2") (pintype "passive"))
      (node (ref "U2") (pin "47") (pinfunction "VSS_2_47") (pintype "power_in"))
    )
    (net (code "102") (name "unconnected-(P6-RFU1-PadA8)") (class "Default")
      (node (ref "P6") (pin "A8") (pinfunction "RFU1_A8") (pintype "bidirectional+no_connect"))
    )
    (net (code "103") (name "unconnected-(P6-RFU1-PadB8)") (class "Default")
      (node (ref "P6") (pin "B8") (pinfunction "RFU1_B8") (pintype "bidirectional+no_connect"))
    )
    (net (code "104") (name "unconnected-(P7-RFU1-PadA8)") (class "Default")
      (node (ref "P7") (pin "A8") (pinfunction "RFU1_A8") (pintype "bidirectional+no_connect"))
    )
    (net (code "105") (name "unconnected-(P7-RFU1-PadB8)") (class "Default")
      (node (ref "P7") (pin "B8") (pinfunction "RFU1_B8") (pintype "bidirectional+no_connect"))
    )
    (net (code "106") (name "unconnected-(P9-RFU1-PadA8)") (class "Default")
      (node (ref "P9") (pin "A8") (pinfunction "RFU1_A8") (pintype "bidirectional+no_connect"))
    )
    (net (code "107") (name "unconnected-(P9-RFU1-PadB8)") (class "Default")
      (node (ref "P9") (pin "B8") (pinfunction "RFU1_B8") (pintype "bidirectional+no_connect"))
    )
    (net (code "108") (name "unconnected-(S1-A1-Pad4)") (class "Default")
      (node (ref "S1") (pin "4") (pinfunction "A1_4") (pintype "passive"))
    )
    (net (code "109") (name "unconnected-(S1-B0-Pad2)") (class "Default")
      (node (ref "S1") (pin "2") (pinfunction "B0_2") (pintype "passive"))
    )
    (net (code "110") (name "unconnected-(S2-A1-Pad4)") (class "Default")
      (node (ref "S2") (pin "4") (pinfunction "A1_4") (pintype "passive"))
    )
    (net (code "111") (name "unconnected-(S2-B0-Pad2)") (class "Default")
      (node (ref "S2") (pin "2") (pinfunction "B0_2") (pintype "passive"))
    )
    (net (code "112") (name "unconnected-(S3-Pad2)") (class "Default")
      (node (ref "S3") (pin "2") (pinfunction "2_2") (pintype "passive"))
    )
    (net (code "113") (name "unconnected-(U3-PA5{slash}UART1_CTS{slash}PA1_(no5V)-Pad2)") (class "Default")
      (node (ref "U3") (pin "2") (pinfunction "PA5/UART1_CTS/PA1_(no5V)_2") (pintype "bidirectional+no_connect"))
    )
    (net (code "114") (name "unconnected-(U3-PB12{slash}SPI2_NSS{slash}CAN2_RX-Pad5)") (class "Default")
      (node (ref "U3") (pin "5") (pinfunction "PB12/SPI2_NSS/CAN2_RX_5") (pintype "bidirectional+no_connect"))
    )
    (net (code "115") (name "unconnected-(U3-PB14{slash}SPI2_MISO{slash}UART3_RTS-Pad7)") (class "Default")
      (node (ref "U3") (pin "7") (pinfunction "PB14/SPI2_MISO/UART3_RTS_7") (pintype "bidirectional+no_connect"))
    )
    (net (code "116") (name "unconnected-(U3-PB15{slash}SPI2_MOSI{slash}UART1_TX-Pad8)") (class "Default")
      (node (ref "U3") (pin "8") (pinfunction "PB15/SPI2_MOSI/UART1_TX_8") (pintype "bidirectional+no_connect"))
    )
  )
)
